# HFX_LFX.net
KiCad netlist of a schematic drawn in Altium Designer
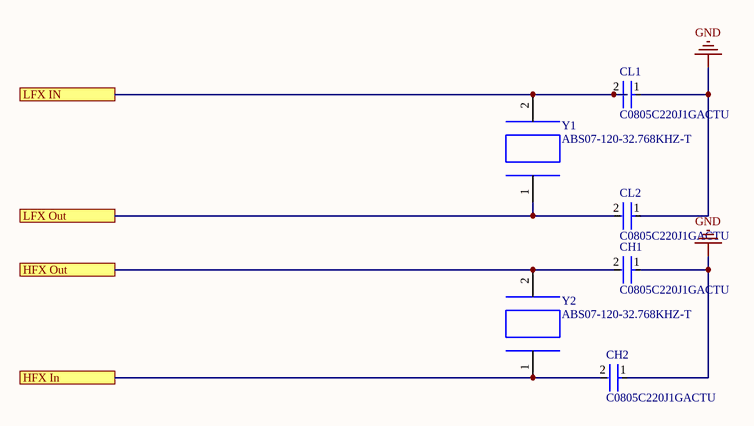
[diagram p0: HFX LFX.SchDoc]

(export (version "E")
  (design (tool "Eeschema 10.0.6"))
  (components
    (comp (ref "CH1")
      (value "C0805C220J1GACTU")
      (footprint "FP-C0805C-DN-MFG")
      (description "CAP CER 22PF 100V 5% NP0 0805")
      (fields
        (field (name "OCTOPART") "https://octopart.com/c0805c220j1gactu-kemet-3791395")
        (field (name "TOLERANCE") "0.05")
      )
      (libsource (lib "Altium Content Vault") (part "b4654b650e69147ec39a6b967a45e02"))
    )
    (comp (ref "CH2")
      (value "C0805C220J1GACTU")
      (footprint "FP-C0805C-DN-MFG")
      (description "CAP CER 22PF 100V 5% NP0 0805")
      (fields
        (field (name "OCTOPART") "https://octopart.com/c0805c220j1gactu-kemet-3791395")
        (field (name "TOLERANCE") "0.05")
      )
      (libsource (lib "Altium Content Vault") (part "b4654b650e69147ec39a6b967a45e02"))
    )
    (comp (ref "CL1")
      (value "C0805C220J1GACTU")
      (footprint "FP-C0805C-DN-MFG")
      (description "CAP CER 22PF 100V 5% NP0 0805")
      (fields
        (field (name "OCTOPART") "https://octopart.com/c0805c220j1gactu-kemet-3791395")
        (field (name "TOLERANCE") "0.05")
      )
      (libsource (lib "Altium Content Vault") (part "b4654b650e69147ec39a6b967a45e02"))
    )
    (comp (ref "CL2")
      (value "C0805C220J1GACTU")
      (footprint "FP-C0805C-DN-MFG")
      (description "CAP CER 22PF 100V 5% NP0 0805")
      (fields
        (field (name "OCTOPART") "https://octopart.com/c0805c220j1gactu-kemet-3791395")
        (field (name "TOLERANCE") "0.05")
      )
      (libsource (lib "Altium Content Vault") (part "b4654b650e69147ec39a6b967a45e02"))
    )
    (comp (ref "Y1")
      (value "ABS07-120-32.768KHZ-T")
      (footprint "XTAL_ABS07-120-32.768KHZ-T")
      (description "32.768kHz Â±20ppm Crystal 6pF 55 kOhms 2-SMD, No Lead")
      (fields (field (name "MF") "Abracon") (field (name "DIGI-KEY_PART_NUMBER") "535-11937-1-ND"))
      (libsource (lib "ABS07-120-32.768KHZ-T") (part "ABS07-120-32.768KHZ-T"))
    )
    (comp (ref "Y2")
      (value "ABS07-120-32.768KHZ-T")
      (footprint "XTAL_ABS07-120-32.768KHZ-T")
      (description "32.768kHz Â±20ppm Crystal 6pF 55 kOhms 2-SMD, No Lead")
      (fields (field (name "MF") "Abracon") (field (name "DIGI-KEY_PART_NUMBER") "535-11937-1-ND"))
      (libsource (lib "ABS07-120-32.768KHZ-T") (part "ABS07-120-32.768KHZ-T"))
    )
  )
  (nets
    (net (code "1") (name "/HFX In") (class "Default")
      (node (ref "CH2") (pin "2") (pinfunction "2_2") (pintype "passive"))
      (node (ref "Y2") (pin "1") (pinfunction "1_1") (pintype "passive"))
    )
    (net (code "2") (name "/HFX Out") (class "Default")
      (node (ref "CH1") (pin "2") (pinfunction "2_2") (pintype "passive"))
      (node (ref "Y2") (pin "2") (pinfunction "2_2") (pintype "passive"))
    )
    (net (code "3") (name "/LFX IN") (class "Default")
      (node (ref "CL1") (pin "2") (pinfunction "2_2") (pintype "passive"))
      (node (ref "Y1") (pin "2") (pinfunction "2_2") (pintype "passive"))
    )
    (net (code "4") (name "/LFX Out") (class "Default")
      (node (ref "CL2") (pin "2") (pinfunction "2_2") (pintype "passive"))
      (node (ref "Y1") (pin "1") (pinfunction "1_1") (pintype "passive"))
    )
    (net (code "5") (name "GND") (class "Default")
      (node (ref "CH1") (pin "1") (pinfunction "1_1") (pintype "passive"))
      (node (ref "CH2") (pin "1") (pinfunction "1_1") (pintype "passive"))
      (node (ref "CL1") (pin "1") (pinfunction "1_1") (pintype "passive"))
      (node (ref "CL2") (pin "1") (pinfunction "1_1") (pintype "passive"))
    )
  )
)
